# Qwiic_4_Pin_Fan_Controller.net
KiCad netlist of a schematic drawn in EAGLE
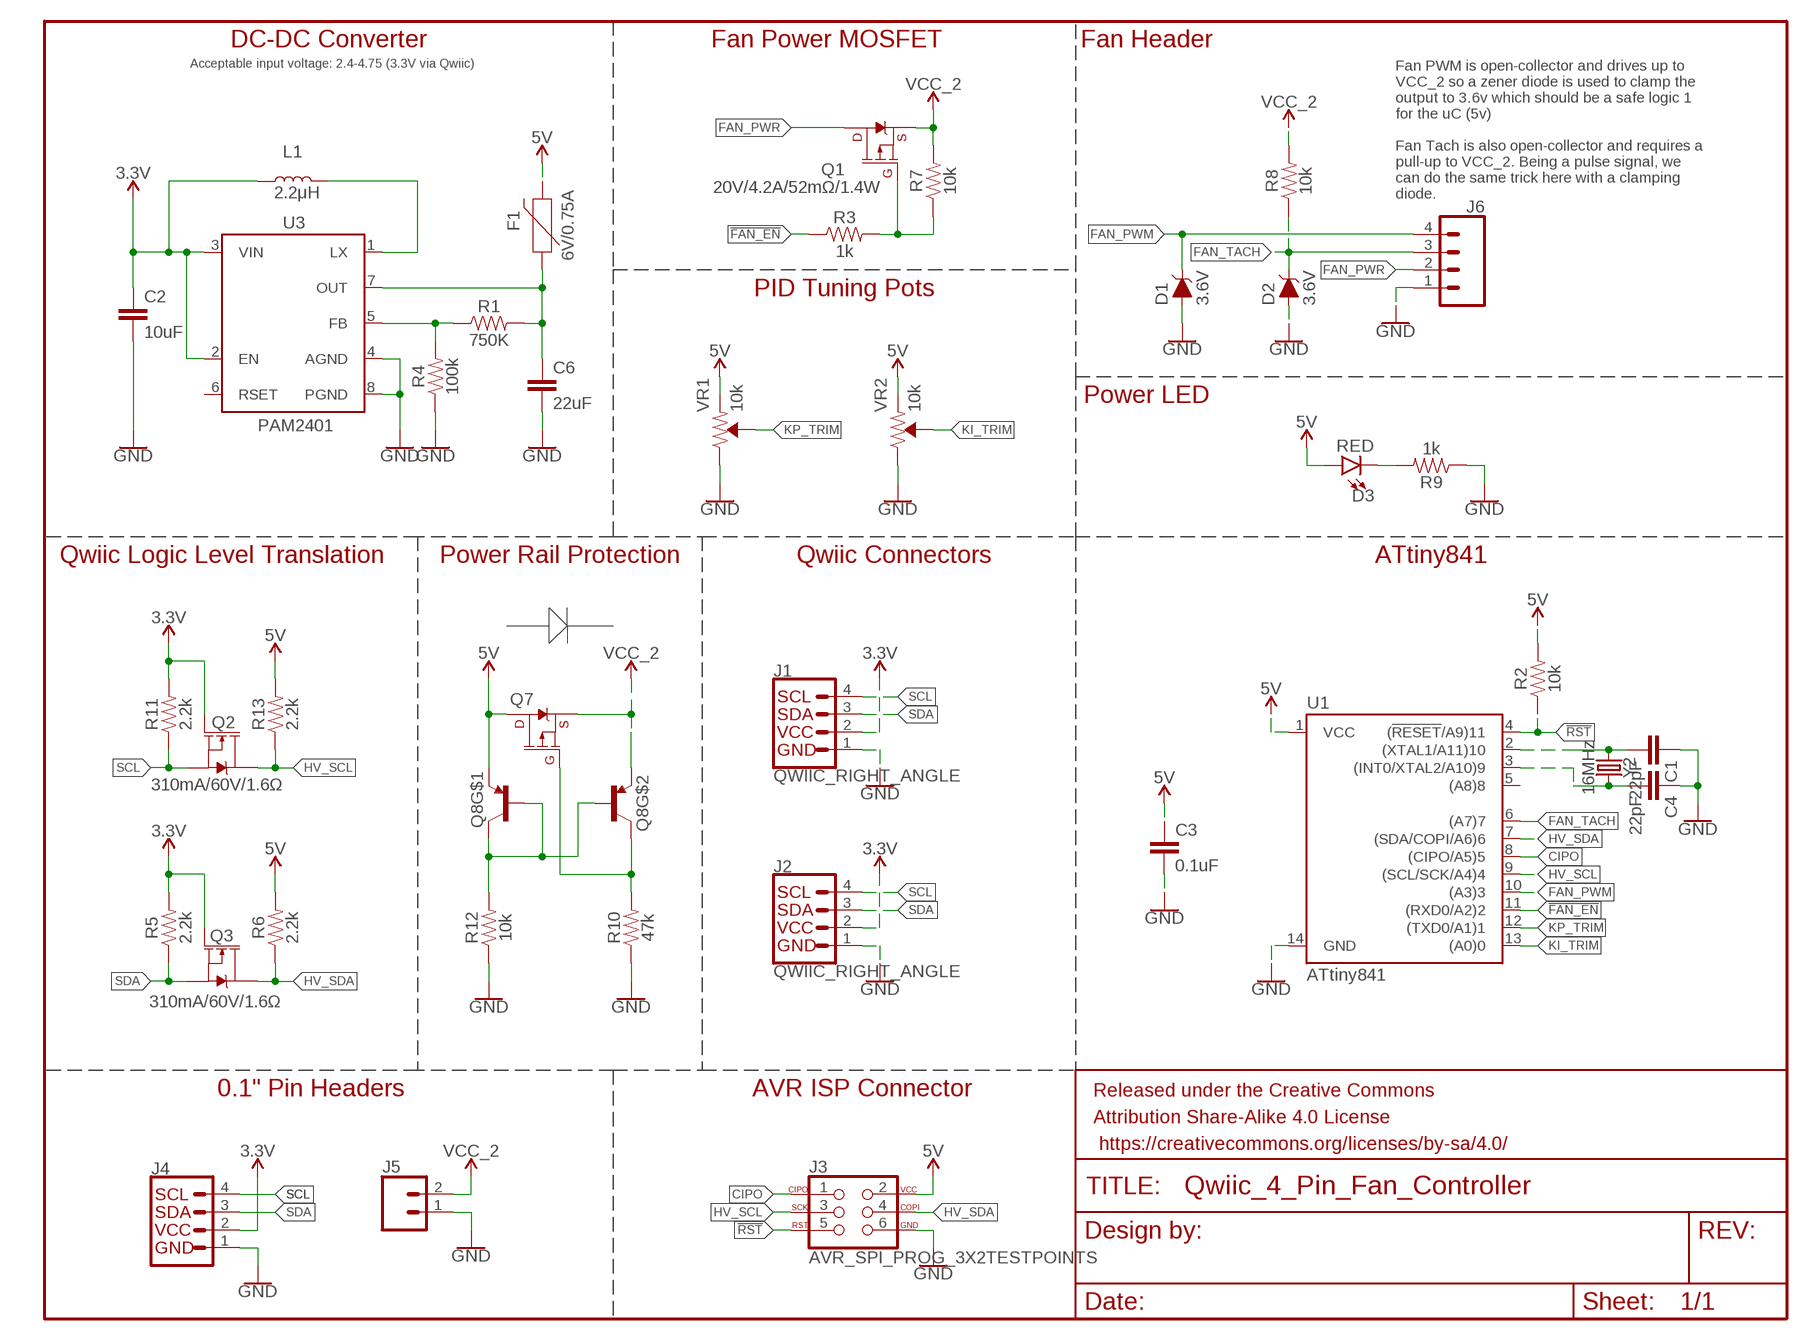
[diagram p0: schematic, sheet 1]

(export (version "E")
  (design (tool "Eeschema 10.0.6"))
  (components
    (comp (ref "C1")
      (value "22pF")
      (footprint "eagle-import:0603")
      (libsource (lib "eagle-import") (part "22PF-0603-50V-5%"))
    )
    (comp (ref "C2")
      (value "10uF")
      (footprint "eagle-import:0603")
      (libsource (lib "eagle-import") (part "10UF-0603-6.3V-20%"))
    )
    (comp (ref "C3")
      (value "0.1uF")
      (footprint "eagle-import:0603")
      (libsource (lib "eagle-import") (part "0.1UF-0603-25V-(+80/-20%)"))
    )
    (comp (ref "C4")
      (value "22pF")
      (footprint "eagle-import:0603")
      (libsource (lib "eagle-import") (part "22PF-0603-50V-5%"))
    )
    (comp (ref "C6")
      (value "22uF")
      (footprint "eagle-import:0805")
      (libsource (lib "eagle-import") (part "22UF-0805-6.3V-20%"))
    )
    (comp (ref "D1")
      (value "3.6V")
      (footprint "eagle-import:SOD-323")
      (libsource (lib "eagle-import") (part "DIODE-ZENER-BZT52C3V6S"))
    )
    (comp (ref "D2")
      (value "3.6V")
      (footprint "eagle-import:SOD-323")
      (libsource (lib "eagle-import") (part "DIODE-ZENER-BZT52C3V6S"))
    )
    (comp (ref "D3")
      (value "RED")
      (footprint "eagle-import:LED-0603")
      (libsource (lib "eagle-import") (part "LED-RED0603"))
    )
    (comp (ref "F1")
      (value "6V/0.75A")
      (footprint "eagle-import:1206")
      (libsource (lib "eagle-import") (part "PPTC_0.75A"))
    )
    (comp (ref "FRAME1")
      (value "FRAME-LETTER")
      (footprint "eagle-import:CREATIVE_COMMONS")
      (libsource (lib "eagle-import") (part "FRAME-LETTER"))
    )
    (comp (ref "J1")
      (value "QWIIC_RIGHT_ANGLE")
      (footprint "eagle-import:JST04_1MM_RA")
      (libsource (lib "eagle-import") (part "QWIIC_CONNECTORJS-1MM"))
    )
    (comp (ref "J2")
      (value "QWIIC_RIGHT_ANGLE")
      (footprint "eagle-import:JST04_1MM_RA")
      (libsource (lib "eagle-import") (part "QWIIC_CONNECTORJS-1MM"))
    )
    (comp (ref "J3")
      (value "AVR_SPI_PROG_3X2TESTPOINTS")
      (footprint "eagle-import:2X3_TEST_POINTS")
      (libsource (lib "eagle-import") (part "AVR_SPI_PROG_3X2TESTPOINTS"))
    )
    (comp (ref "J4")
      (value "I2C_STANDARD_NO_SILK")
      (footprint "eagle-import:1X04_NO_SILK")
      (libsource (lib "eagle-import") (part "I2C_STANDARD_NO_SILK"))
    )
    (comp (ref "J5")
      (value "CONN_021X02_NO_SILK")
      (footprint "eagle-import:1X02_NO_SILK")
      (libsource (lib "eagle-import") (part "CONN_021X02_NO_SILK"))
    )
    (comp (ref "J6")
      (value "CONN_041X04_NO_SILK")
      (footprint "eagle-import:1X04_NO_SILK")
      (libsource (lib "eagle-import") (part "CONN_041X04_NO_SILK"))
    )
    (comp (ref "L1")
      (value "2.2μH")
      (footprint "eagle-import:0806")
      (libsource (lib "eagle-import") (part "2.2μH_SHIELDED_INDUCTOR"))
    )
    (comp (ref "Q1")
      (value "20V/4.2A/52mΩ/1.4W")
      (footprint "eagle-import:SOT23-3")
      (libsource (lib "eagle-import") (part "MOSFET_PCH-DMG2305UX-7"))
    )
    (comp (ref "Q2")
      (value "310mA/60V/1.6Ω")
      (footprint "eagle-import:SOT323")
      (libsource (lib "eagle-import") (part "MOSFET-NCH-2N7002PW"))
    )
    (comp (ref "Q3")
      (value "310mA/60V/1.6Ω")
      (footprint "eagle-import:SOT323")
      (libsource (lib "eagle-import") (part "MOSFET-NCH-2N7002PW"))
    )
    (comp (ref "Q7")
      (value "20V/4.2A/52mΩ/1.4W")
      (footprint "eagle-import:SOT23-3")
      (libsource (lib "eagle-import") (part "MOSFET_PCH-DMG2305UX-7"))
    )
    (comp (ref "Q8")
      (value "TRANS_PNP_DUALSOT-363")
      (footprint "eagle-import:SOT363_PHILIPS")
      (libsource (lib "eagle-import") (part "TRANS_PNP_DUALSOT-363"))
    )
    (comp (ref "R1")
      (value "750K")
      (footprint "eagle-import:0603")
      (libsource (lib "eagle-import") (part "750KOHM-0603-1/10W-1%"))
    )
    (comp (ref "R2")
      (value "10k")
      (footprint "eagle-import:0603@1")
      (libsource (lib "eagle-import") (part "10KOHM-0603-1/10W-1%"))
    )
    (comp (ref "R3")
      (value "1k")
      (footprint "eagle-import:0603")
      (libsource (lib "eagle-import") (part "1KOHM-0603-1/10W-1%"))
    )
    (comp (ref "R4")
      (value "100k")
      (footprint "eagle-import:0603")
      (libsource (lib "eagle-import") (part "100KOHM-0603-1/10W-1%"))
    )
    (comp (ref "R5")
      (value "2.2k")
      (footprint "eagle-import:0603")
      (libsource (lib "eagle-import") (part "2.2KOHM-0603-1/10W-1%"))
    )
    (comp (ref "R6")
      (value "2.2k")
      (footprint "eagle-import:0603")
      (libsource (lib "eagle-import") (part "2.2KOHM-0603-1/10W-1%"))
    )
    (comp (ref "R7")
      (value "10k")
      (footprint "eagle-import:0603@1")
      (libsource (lib "eagle-import") (part "10KOHM-0603-1/10W-1%"))
    )
    (comp (ref "R8")
      (value "10k")
      (footprint "eagle-import:0603@1")
      (libsource (lib "eagle-import") (part "10KOHM-0603-1/10W-1%"))
    )
    (comp (ref "R9")
      (value "1k")
      (footprint "eagle-import:0603")
      (libsource (lib "eagle-import") (part "1KOHM-0603-1/10W-1%"))
    )
    (comp (ref "R10")
      (value "47k")
      (footprint "eagle-import:0603@1")
      (libsource (lib "eagle-import") (part "47KOHM-0603-1/10W-1%"))
    )
    (comp (ref "R11")
      (value "2.2k")
      (footprint "eagle-import:0603")
      (libsource (lib "eagle-import") (part "2.2KOHM-0603-1/10W-1%"))
    )
    (comp (ref "R12")
      (value "10k")
      (footprint "eagle-import:0603@1")
      (libsource (lib "eagle-import") (part "10KOHM-0603-1/10W-1%"))
    )
    (comp (ref "R13")
      (value "2.2k")
      (footprint "eagle-import:0603")
      (libsource (lib "eagle-import") (part "2.2KOHM-0603-1/10W-1%"))
    )
    (comp (ref "U1")
      (value "ATtiny841")
      (footprint "eagle-import:SO14")
      (libsource (lib "eagle-import") (part "ATTINY841-ARDUINO"))
    )
    (comp (ref "U3")
      (value "PAM2401")
      (footprint "eagle-import:MSOP8")
      (libsource (lib "eagle-import") (part "PAM2401"))
    )
    (comp (ref "VR1")
      (value "10k")
      (footprint "eagle-import:TRIMPOT-SMD-3MM-CLOSED")
      (libsource (lib "eagle-import") (part "TRIMPOT-SMD-3MM-CLOSED-1/8W-20%"))
    )
    (comp (ref "VR2")
      (value "10k")
      (footprint "eagle-import:TRIMPOT-SMD-3MM-CLOSED")
      (libsource (lib "eagle-import") (part "TRIMPOT-SMD-3MM-CLOSED-1/8W-20%"))
    )
    (comp (ref "Y2")
      (value "16MHz")
      (footprint "eagle-import:CRYSTAL-SMD-2.0X1.6MM")
      (libsource (lib "eagle-import") (part "CRYSTAL-16MHZSMD-2X1.6"))
    )
  )
  (nets
    (net (code "1") (name "/~{FAN_EN}") (class "Default")
      (node (ref "R3") (pin "1") (pinfunction "1_1") (pintype "passive"))
      (node (ref "U1") (pin "11") (pinfunction "(RXD0/A2)2_11") (pintype "bidirectional"))
    )
    (net (code "2") (name "/~{RST}") (class "Default")
      (node (ref "J3") (pin "5") (pinfunction "5_5") (pintype "passive"))
      (node (ref "R2") (pin "1") (pinfunction "1_1") (pintype "passive"))
      (node (ref "U1") (pin "4") (pinfunction "(~{RESET}/A9)11_4") (pintype "bidirectional"))
    )
    (net (code "3") (name "3.3V") (class "Default")
      (node (ref "C2") (pin "1") (pinfunction "1_1") (pintype "passive"))
      (node (ref "J1") (pin "2") (pinfunction "2_2") (pintype "power_in"))
      (node (ref "J2") (pin "2") (pinfunction "2_2") (pintype "power_in"))
      (node (ref "J4") (pin "2") (pinfunction "2_2") (pintype "power_in"))
      (node (ref "L1") (pin "1") (pinfunction "1_1") (pintype "passive"))
      (node (ref "Q2") (pin "1") (pinfunction "G_1") (pintype "bidirectional"))
      (node (ref "Q3") (pin "1") (pinfunction "G_1") (pintype "bidirectional"))
      (node (ref "R11") (pin "2") (pinfunction "2_2") (pintype "passive"))
      (node (ref "R5") (pin "2") (pinfunction "2_2") (pintype "passive"))
      (node (ref "U3") (pin "2") (pinfunction "EN_2") (pintype "bidirectional"))
      (node (ref "U3") (pin "3") (pinfunction "VIN_3") (pintype "bidirectional"))
    )
    (net (code "4") (name "5V") (class "Default")
      (node (ref "C3") (pin "1") (pinfunction "1_1") (pintype "passive"))
      (node (ref "D3") (pin "A") (pinfunction "A_A") (pintype "passive"))
      (node (ref "F1") (pin "2") (pinfunction "2_2") (pintype "bidirectional"))
      (node (ref "J3") (pin "2") (pinfunction "2_2") (pintype "passive"))
      (node (ref "Q7") (pin "3") (pinfunction "D_3") (pintype "bidirectional"))
      (node (ref "Q8") (pin "1") (pinfunction "E_1") (pintype "passive"))
      (node (ref "R13") (pin "2") (pinfunction "2_2") (pintype "passive"))
      (node (ref "R2") (pin "2") (pinfunction "2_2") (pintype "passive"))
      (node (ref "R6") (pin "2") (pinfunction "2_2") (pintype "passive"))
      (node (ref "U1") (pin "1") (pinfunction "VCC_1") (pintype "power_in"))
      (node (ref "VR1") (pin "1") (pinfunction "CCW_1") (pintype "passive"))
      (node (ref "VR2") (pin "1") (pinfunction "CCW_1") (pintype "passive"))
    )
    (net (code "5") (name "CIPO") (class "Default")
      (node (ref "J3") (pin "1") (pinfunction "1_1") (pintype "passive"))
      (node (ref "U1") (pin "8") (pinfunction "(CIPO/A5)5_8") (pintype "bidirectional"))
    )
    (net (code "6") (name "FAN_PWM") (class "Default")
      (node (ref "D1") (pin "C") (pinfunction "C_C") (pintype "passive"))
      (node (ref "J6") (pin "4") (pinfunction "4_4") (pintype "passive"))
      (node (ref "U1") (pin "10") (pinfunction "(A3)3_10") (pintype "bidirectional"))
    )
    (net (code "7") (name "FAN_PWR") (class "Default")
      (node (ref "J6") (pin "2") (pinfunction "2_2") (pintype "passive"))
      (node (ref "Q1") (pin "3") (pinfunction "D_3") (pintype "bidirectional"))
    )
    (net (code "8") (name "FAN_TACH") (class "Default")
      (node (ref "D2") (pin "C") (pinfunction "C_C") (pintype "passive"))
      (node (ref "J6") (pin "3") (pinfunction "3_3") (pintype "passive"))
      (node (ref "R8") (pin "1") (pinfunction "1_1") (pintype "passive"))
      (node (ref "U1") (pin "6") (pinfunction "(A7)7_6") (pintype "bidirectional"))
    )
    (net (code "9") (name "GND") (class "Default")
      (node (ref "C1") (pin "1") (pinfunction "1_1") (pintype "passive"))
      (node (ref "C2") (pin "2") (pinfunction "2_2") (pintype "passive"))
      (node (ref "C3") (pin "2") (pinfunction "2_2") (pintype "passive"))
      (node (ref "C4") (pin "1") (pinfunction "1_1") (pintype "passive"))
      (node (ref "C6") (pin "2") (pinfunction "2_2") (pintype "passive"))
      (node (ref "D1") (pin "A") (pinfunction "A_A") (pintype "passive"))
      (node (ref "D2") (pin "A") (pinfunction "A_A") (pintype "passive"))
      (node (ref "J1") (pin "1") (pinfunction "1_1") (pintype "power_in"))
      (node (ref "J2") (pin "1") (pinfunction "1_1") (pintype "power_in"))
      (node (ref "J3") (pin "6") (pinfunction "6_6") (pintype "passive"))
      (node (ref "J4") (pin "1") (pinfunction "1_1") (pintype "power_in"))
      (node (ref "J5") (pin "1") (pinfunction "1_1") (pintype "passive"))
      (node (ref "J6") (pin "1") (pinfunction "1_1") (pintype "passive"))
      (node (ref "R10") (pin "1") (pinfunction "1_1") (pintype "passive"))
      (node (ref "R12") (pin "1") (pinfunction "1_1") (pintype "passive"))
      (node (ref "R4") (pin "1") (pinfunction "1_1") (pintype "passive"))
      (node (ref "R9") (pin "1") (pinfunction "1_1") (pintype "passive"))
      (node (ref "U1") (pin "14") (pinfunction "GND_14") (pintype "power_in"))
      (node (ref "U3") (pin "4") (pinfunction "AGND_4") (pintype "bidirectional"))
      (node (ref "U3") (pin "8") (pinfunction "PGND_8") (pintype "bidirectional"))
      (node (ref "VR1") (pin "3") (pinfunction "CW_3") (pintype "passive"))
      (node (ref "VR2") (pin "3") (pinfunction "CW_3") (pintype "passive"))
    )
    (net (code "10") (name "HV_SCL") (class "Default")
      (node (ref "J3") (pin "3") (pinfunction "3_3") (pintype "passive"))
      (node (ref "Q2") (pin "3") (pinfunction "D_3") (pintype "bidirectional"))
      (node (ref "R13") (pin "1") (pinfunction "1_1") (pintype "passive"))
      (node (ref "U1") (pin "9") (pinfunction "(SCL/SCK/A4)4_9") (pintype "bidirectional"))
    )
    (net (code "11") (name "HV_SDA") (class "Default")
      (node (ref "J3") (pin "4") (pinfunction "4_4") (pintype "passive"))
      (node (ref "Q3") (pin "3") (pinfunction "D_3") (pintype "bidirectional"))
      (node (ref "R6") (pin "1") (pinfunction "1_1") (pintype "passive"))
      (node (ref "U1") (pin "7") (pinfunction "(SDA/COPI/A6)6_7") (pintype "bidirectional"))
    )
    (net (code "12") (name "KI_TRIM") (class "Default")
      (node (ref "U1") (pin "13") (pinfunction "(A0)0_13") (pintype "bidirectional"))
      (node (ref "VR2") (pin "2") (pinfunction "WIPER_2") (pintype "passive"))
    )
    (net (code "13") (name "KP_TRIM") (class "Default")
      (node (ref "U1") (pin "12") (pinfunction "(TXD0/A1)1_12") (pintype "bidirectional"))
      (node (ref "VR1") (pin "2") (pinfunction "WIPER_2") (pintype "passive"))
    )
    (net (code "14") (name "Net-(D3-PadC)") (class "Default")
      (node (ref "D3") (pin "C") (pinfunction "C_C") (pintype "passive"))
      (node (ref "R9") (pin "2") (pinfunction "2_2") (pintype "passive"))
    )
    (net (code "15") (name "Net-(Q1-G)") (class "Default")
      (node (ref "Q1") (pin "1") (pinfunction "G_1") (pintype "bidirectional"))
      (node (ref "R3") (pin "2") (pinfunction "2_2") (pintype "passive"))
      (node (ref "R7") (pin "1") (pinfunction "1_1") (pintype "passive"))
    )
    (net (code "16") (name "Net-(Q7-G)") (class "Default")
      (node (ref "Q7") (pin "1") (pinfunction "G_1") (pintype "bidirectional"))
      (node (ref "Q8") (pin "3") (pinfunction "C_3") (pintype "passive"))
      (node (ref "R10") (pin "2") (pinfunction "2_2") (pintype "passive"))
    )
    (net (code "17") (name "Net-(Q8A-B)") (class "Default")
      (node (ref "Q8") (pin "2") (pinfunction "B_2") (pintype "passive"))
      (node (ref "Q8") (pin "5") (pinfunction "B_5") (pintype "passive"))
      (node (ref "Q8") (pin "6") (pinfunction "C_6") (pintype "passive"))
      (node (ref "R12") (pin "2") (pinfunction "2_2") (pintype "passive"))
    )
    (net (code "18") (name "Net-(U1-(INT0{slash}XTAL2{slash}A10)9)") (class "Default")
      (node (ref "C4") (pin "2") (pinfunction "2_2") (pintype "passive"))
      (node (ref "U1") (pin "3") (pinfunction "(INT0/XTAL2/A10)9_3") (pintype "bidirectional"))
      (node (ref "Y2") (pin "1") (pinfunction "1_1") (pintype "passive"))
    )
    (net (code "19") (name "Net-(U1-(XTAL1{slash}A11)10)") (class "Default")
      (node (ref "C1") (pin "2") (pinfunction "2_2") (pintype "passive"))
      (node (ref "U1") (pin "2") (pinfunction "(XTAL1/A11)10_2") (pintype "bidirectional"))
      (node (ref "Y2") (pin "3") (pinfunction "2_3") (pintype "passive"))
    )
    (net (code "20") (name "Net-(U3-FB)") (class "Default")
      (node (ref "R1") (pin "1") (pinfunction "1_1") (pintype "passive"))
      (node (ref "R4") (pin "2") (pinfunction "2_2") (pintype "passive"))
      (node (ref "U3") (pin "5") (pinfunction "FB_5") (pintype "bidirectional"))
    )
    (net (code "21") (name "Net-(U3-LX)") (class "Default")
      (node (ref "L1") (pin "2") (pinfunction "2_2") (pintype "passive"))
      (node (ref "U3") (pin "1") (pinfunction "LX_1") (pintype "bidirectional"))
    )
    (net (code "22") (name "Net-(U3-OUT)") (class "Default")
      (node (ref "C6") (pin "1") (pinfunction "1_1") (pintype "passive"))
      (node (ref "F1") (pin "1") (pinfunction "1_1") (pintype "bidirectional"))
      (node (ref "R1") (pin "2") (pinfunction "2_2") (pintype "passive"))
      (node (ref "U3") (pin "7") (pinfunction "OUT_7") (pintype "bidirectional"))
    )
    (net (code "23") (name "SCL") (class "Default")
      (node (ref "J1") (pin "4") (pinfunction "4_4") (pintype "passive"))
      (node (ref "J2") (pin "4") (pinfunction "4_4") (pintype "passive"))
      (node (ref "J4") (pin "4") (pinfunction "4_4") (pintype "passive"))
      (node (ref "Q2") (pin "2") (pinfunction "S_2") (pintype "bidirectional"))
      (node (ref "R11") (pin "1") (pinfunction "1_1") (pintype "passive"))
    )
    (net (code "24") (name "SDA") (class "Default")
      (node (ref "J1") (pin "3") (pinfunction "3_3") (pintype "passive"))
      (node (ref "J2") (pin "3") (pinfunction "3_3") (pintype "passive"))
      (node (ref "J4") (pin "3") (pinfunction "3_3") (pintype "passive"))
      (node (ref "Q3") (pin "2") (pinfunction "S_2") (pintype "bidirectional"))
      (node (ref "R5") (pin "1") (pinfunction "1_1") (pintype "passive"))
    )
    (net (code "25") (name "VCC_2") (class "Default")
      (node (ref "J5") (pin "2") (pinfunction "2_2") (pintype "passive"))
      (node (ref "Q1") (pin "2") (pinfunction "S_2") (pintype "bidirectional"))
      (node (ref "Q7") (pin "2") (pinfunction "S_2") (pintype "bidirectional"))
      (node (ref "Q8") (pin "4") (pinfunction "E_4") (pintype "passive"))
      (node (ref "R7") (pin "2") (pinfunction "2_2") (pintype "passive"))
      (node (ref "R8") (pin "2") (pinfunction "2_2") (pintype "passive"))
    )
    (net (code "26") (name "unconnected-(U1-(A8)8-Pad5)") (class "Default")
      (node (ref "U1") (pin "5") (pinfunction "(A8)8_5") (pintype "bidirectional"))
    )
    (net (code "27") (name "unconnected-(U3-RSET-Pad6)") (class "Default")
      (node (ref "U3") (pin "6") (pinfunction "RSET_6") (pintype "bidirectional"))
    )
  )
)
